# Module_Hub.net
KiCad netlist of a schematic drawn in Altium Designer
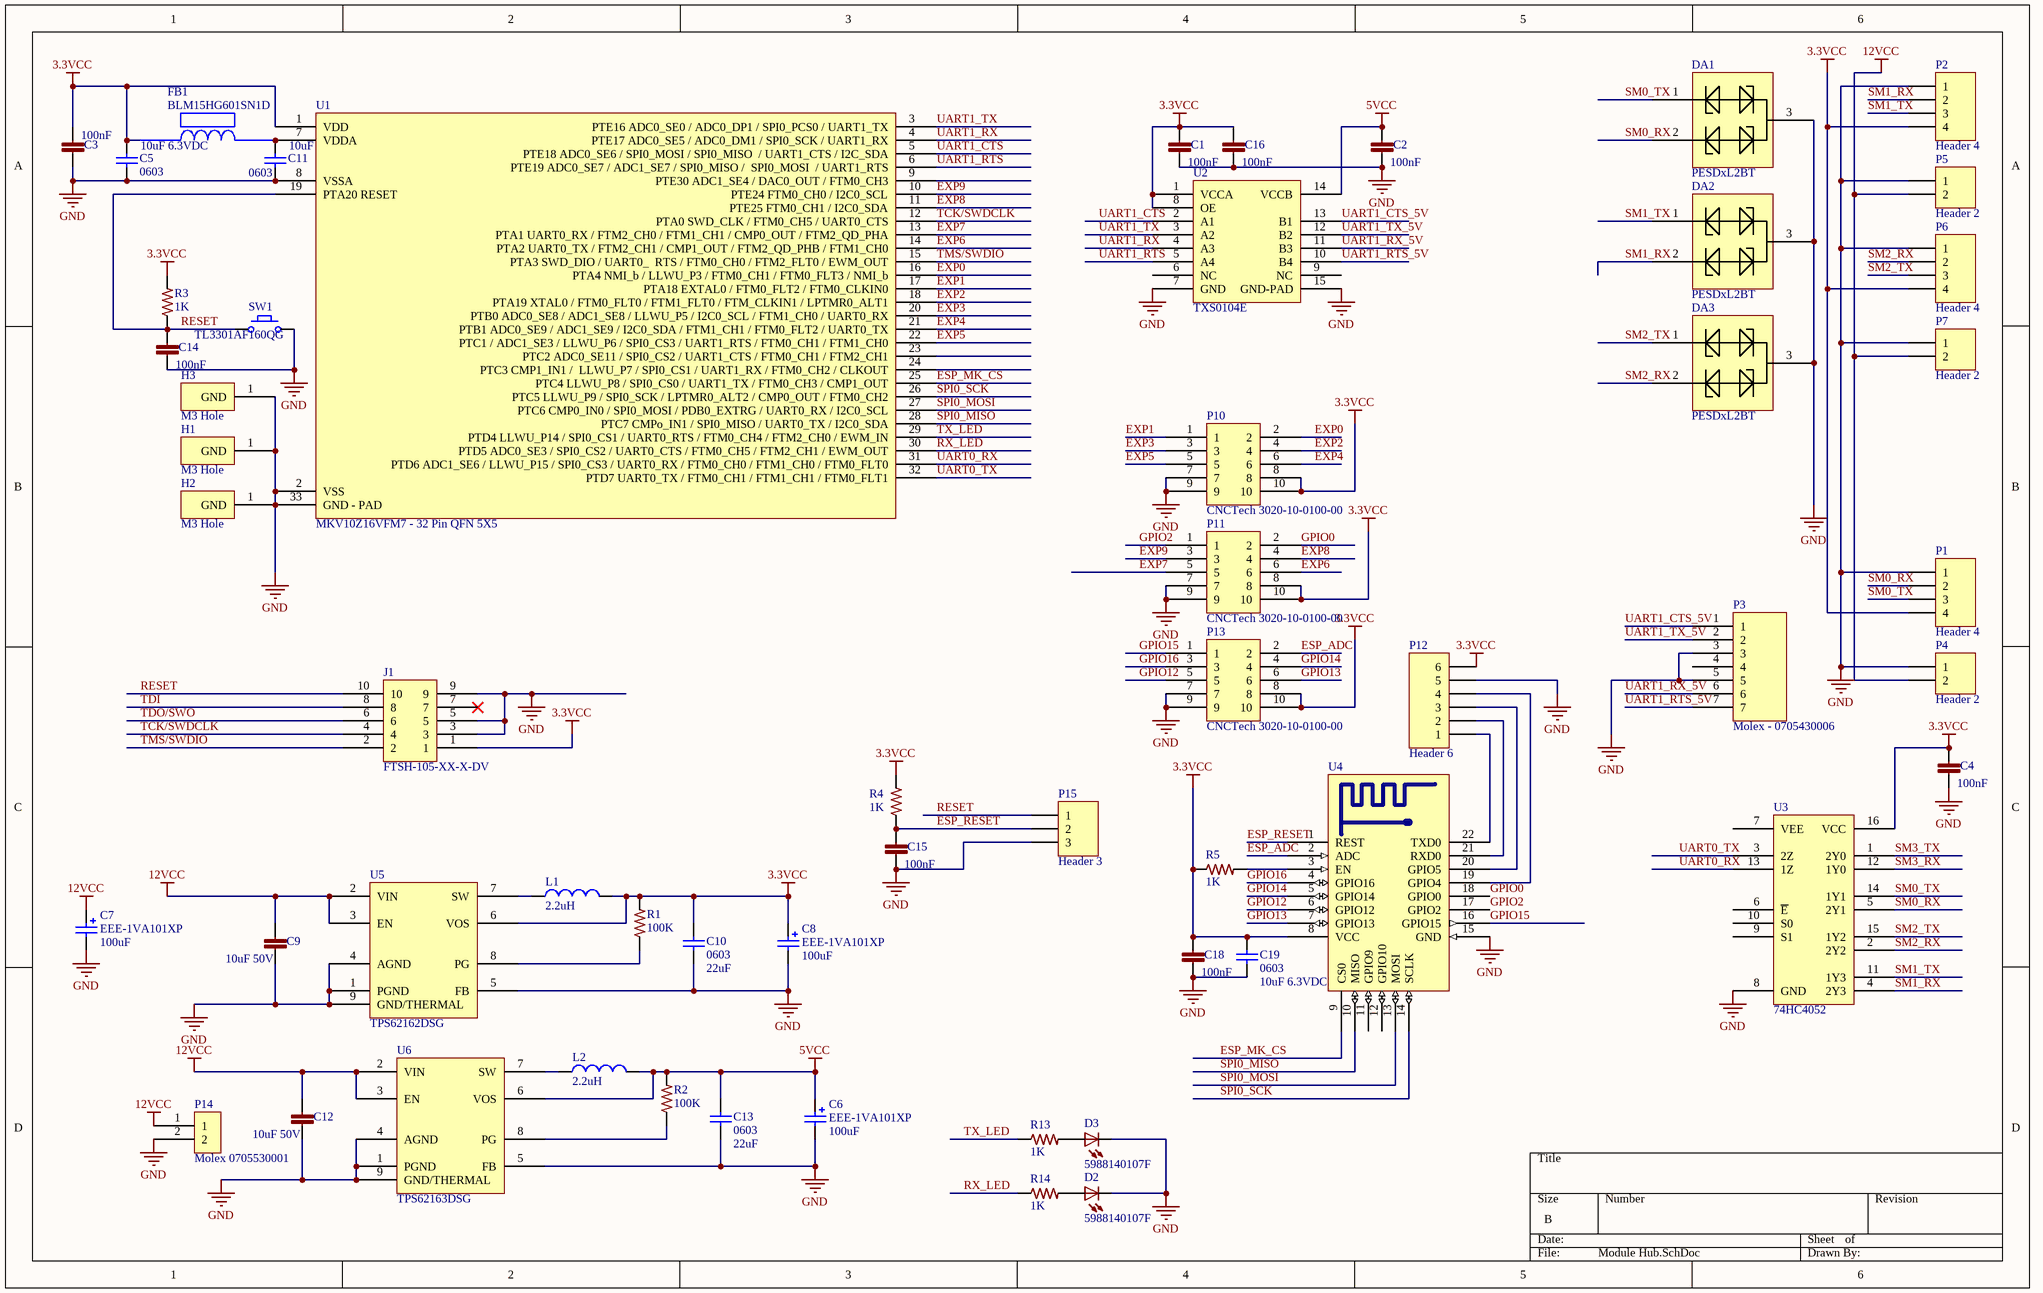
[diagram p0: Module Hub.SchDoc]

(export (version "E")
  (design (tool "Eeschema 10.0.6"))
  (components
    (comp (ref "C1")
      (value "100nF")
      (footprint "C0603")
      (description "CAP CER 0603 100nF 50V 10% X7R")
      (fields
        (field (name "MANUFACTURERPARTNUMBER") "C0603C104K5RACTU")
        (field (name "PUBLISHER") "UltiMachine")
      )
      (libsource (lib "3Delight") (part "C0603C104K5RACTU"))
    )
    (comp (ref "C2")
      (value "100nF")
      (footprint "C0603")
      (description "CAP CER 0603 100nF 50V 10% X7R")
      (fields
        (field (name "MANUFACTURERPARTNUMBER") "C0603C104K5RACTU")
        (field (name "PUBLISHER") "UltiMachine")
      )
      (libsource (lib "3Delight") (part "C0603C104K5RACTU"))
    )
    (comp (ref "C3")
      (value "100nF")
      (footprint "C0603")
      (description "CAP CER 0603 100nF 50V 10% X7R")
      (fields
        (field (name "MANUFACTURERPARTNUMBER") "C0603C104K5RACTU")
        (field (name "PUBLISHER") "UltiMachine")
      )
      (libsource (lib "3Delight") (part "C0603C104K5RACTU"))
    )
    (comp (ref "C4")
      (value "100nF")
      (footprint "C0603")
      (description "CAP CER 0603 100nF 50V 10% X7R")
      (fields
        (field (name "MANUFACTURERPARTNUMBER") "C0603C104K5RACTU")
        (field (name "PUBLISHER") "UltiMachine")
      )
      (libsource (lib "3Delight") (part "C0603C104K5RACTU"))
    )
    (comp (ref "C5")
      (value "0603")
      (footprint "C0603")
      (description "CAP CER 10UF 6.3V 10% JB 0603")
      (fields
        (field (name "MFR PART #") "C1608JB0J106K080AB")
        (field (name "MFR") "TDK")
        (field (name "ALTIUM_VALUE") "10uF 6.3VDC")
      )
      (libsource (lib "Tigershark3D") (part "C1608JB0J106K080AB"))
    )
    (comp (ref "C6")
      (value "EEE-1VA101XP")
      (footprint "EEE-1VA101XP")
      (description "CAP ALUM 100UF 35V 20% SMD")
      (fields (field (name "DIGIKEY PART #") "PCE3951CT-ND") (field (name "ALTIUM_VALUE") "100uF"))
      (libsource (lib "Tigershark3D") (part "EEE-1VA101XP"))
    )
    (comp (ref "C7")
      (value "EEE-1VA101XP")
      (footprint "EEE-1VA101XP")
      (description "CAP ALUM 100UF 35V 20% SMD")
      (fields (field (name "DIGIKEY PART #") "PCE3951CT-ND") (field (name "ALTIUM_VALUE") "100uF"))
      (libsource (lib "Tigershark3D") (part "EEE-1VA101XP"))
    )
    (comp (ref "C8")
      (value "EEE-1VA101XP")
      (footprint "EEE-1VA101XP")
      (description "CAP ALUM 100UF 35V 20% SMD")
      (fields (field (name "DIGIKEY PART #") "PCE3951CT-ND") (field (name "ALTIUM_VALUE") "100uF"))
      (libsource (lib "Tigershark3D") (part "EEE-1VA101XP"))
    )
    (comp (ref "C9")
      (value "10uF 50V")
      (footprint "C1206")
      (description "CAP CER 10UF 50V 10% X5R 1206")
      (fields
        (field (name "MANUFACTURER") "Samsung")
        (field (name "MANUFACTURERPARTNUMBER") "CL31A106KBHNNNE")
        (field (name "PUBLISHER") "UltiMachine")
      )
      (libsource (lib "Tigershark3D") (part "CL31A106KBHNNNE"))
    )
    (comp (ref "C10")
      (value "0603")
      (footprint "C0805")
      (description "CAP CER 22UF 6.3V 10% X5R 0805")
      (fields
        (field (name "MFR PART #") "CL21A226KQQNNNE")
        (field (name "MFR") "Samsung")
        (field (name "ALTIUM_VALUE") "22uF")
      )
      (libsource (lib "Sensor Package") (part "CL21A226KQQNNNE"))
    )
    (comp (ref "C11")
      (value "0603")
      (footprint "C0603")
      (description "CAP CER 10UF 6.3V 10% JB 0603")
      (fields
        (field (name "MFR PART #") "C1608JB0J106K080AB")
        (field (name "MFR") "TDK")
        (field (name "ALTIUM_VALUE") "10uF")
      )
      (libsource (lib "Tigershark3D") (part "C1608JB0J106K080AB"))
    )
    (comp (ref "C12")
      (value "10uF 50V")
      (footprint "C1206")
      (description "CAP CER 10UF 50V 10% X5R 1206")
      (fields
        (field (name "MANUFACTURER") "Samsung")
        (field (name "MANUFACTURERPARTNUMBER") "CL31A106KBHNNNE")
        (field (name "PUBLISHER") "UltiMachine")
      )
      (libsource (lib "Tigershark3D") (part "CL31A106KBHNNNE"))
    )
    (comp (ref "C13")
      (value "0603")
      (footprint "C0805")
      (description "CAP CER 22UF 6.3V 10% X5R 0805")
      (fields
        (field (name "MFR PART #") "CL21A226KQQNNNE")
        (field (name "MFR") "Samsung")
        (field (name "ALTIUM_VALUE") "22uF")
      )
      (libsource (lib "Sensor Package") (part "CL21A226KQQNNNE"))
    )
    (comp (ref "C14")
      (value "100nF")
      (footprint "C0402")
      (description "CAP CER 0402 100nF 16V 10% X7R")
      (fields
        (field (name "MANUFACTURERPARTNUMBER") "GRM155R71C104KA88D")
        (field (name "PUBLISHER") "UltiMachine")
      )
      (libsource (lib "3Delight") (part "GRM155R71C104KA88D"))
    )
    (comp (ref "C15")
      (value "100nF")
      (footprint "C0402")
      (description "CAP CER 0402 100nF 16V 10% X7R")
      (fields
        (field (name "MANUFACTURERPARTNUMBER") "GRM155R71C104KA88D")
        (field (name "PUBLISHER") "UltiMachine")
      )
      (libsource (lib "3Delight") (part "GRM155R71C104KA88D"))
    )
    (comp (ref "C16")
      (value "100nF")
      (footprint "C0603")
      (description "CAP CER 0603 100nF 50V 10% X7R")
      (fields
        (field (name "MANUFACTURERPARTNUMBER") "C0603C104K5RACTU")
        (field (name "PUBLISHER") "UltiMachine")
      )
      (libsource (lib "3Delight") (part "C0603C104K5RACTU"))
    )
    (comp (ref "C18")
      (value "100nF")
      (footprint "C0603")
      (description "CAP CER 0603 100nF 50V 10% X7R")
      (fields
        (field (name "MANUFACTURERPARTNUMBER") "C0603C104K5RACTU")
        (field (name "PUBLISHER") "UltiMachine")
      )
      (libsource (lib "3Delight") (part "C0603C104K5RACTU"))
    )
    (comp (ref "C19")
      (value "0603")
      (footprint "C0603")
      (description "CAP CER 10UF 6.3V 10% JB 0603")
      (fields
        (field (name "MFR PART #") "C1608JB0J106K080AB")
        (field (name "MFR") "TDK")
        (field (name "ALTIUM_VALUE") "10uF 6.3VDC")
      )
      (libsource (lib "Tigershark3D") (part "C1608JB0J106K080AB"))
    )
    (comp (ref "D2")
      (value "5988140107F")
      (footprint "LED2012120")
      (description "LED 0805 Yellow")
      (fields (field (name "PUBLISHER") "UltiMachine"))
      (libsource (lib "Tigershark3D") (part "5988140107F"))
    )
    (comp (ref "D3")
      (value "5988140107F")
      (footprint "LED2012120")
      (description "LED 0805 Yellow")
      (fields (field (name "PUBLISHER") "UltiMachine"))
      (libsource (lib "Tigershark3D") (part "5988140107F"))
    )
    (comp (ref "DA1")
      (value "PESDxL2BT")
      (footprint "SOT95P230X110-3N")
      (description "PESDxL2BT TVS Diode Array 2x")
      (libsource (lib "ZMBo Schematic Library") (part "PESDxL2BT"))
    )
    (comp (ref "DA2")
      (value "PESDxL2BT")
      (footprint "SOT95P230X110-3N")
      (description "PESDxL2BT TVS Diode Array 2x")
      (libsource (lib "ZMBo Schematic Library") (part "PESDxL2BT"))
    )
    (comp (ref "DA3")
      (value "PESDxL2BT")
      (footprint "SOT95P230X110-3N")
      (description "PESDxL2BT TVS Diode Array 2x")
      (libsource (lib "ZMBo Schematic Library") (part "PESDxL2BT"))
    )
    (comp (ref "FB1")
      (value "BLM15HG601SN1D")
      (footprint "BLM18PG121SN1D")
      (libsource (lib "AHD Part Library") (part "BLM15HG601SN1D"))
    )
    (comp (ref "H1")
      (value "M3 Hole")
      (footprint "Hole-3mm")
      (description "3mm Hole")
      (libsource (lib "Sensor Package") (part "Hole"))
    )
    (comp (ref "H2")
      (value "M3 Hole")
      (footprint "Hole-3mm")
      (description "3mm Hole")
      (libsource (lib "Sensor Package") (part "Hole"))
    )
    (comp (ref "H3")
      (value "M3 Hole")
      (footprint "Hole-3mm")
      (description "3mm Hole")
      (libsource (lib "Sensor Package") (part "Hole"))
    )
    (comp (ref "J1")
      (value "FTSH-105-XX-X-DV")
      (footprint "FTSH-105-XX-X-DV")
      (libsource (lib "Adams Altium Library") (part "ARM Cortex JTAG-DEBUG Header"))
    )
    (comp (ref "L1")
      (value "2.2uH")
      (footprint "VLS252012T-2R2M1R3")
      (description "VLS252012T-2R2M1R3")
      (fields (field (name "MFR") "TDK Corporation") (field (name "PUBLISHER") "Adam Vadala-Roth"))
      (libsource (lib "Sensor Package") (part "VLS252012T-2R2M1R3"))
    )
    (comp (ref "L2")
      (value "2.2uH")
      (footprint "VLS252012T-2R2M1R3")
      (description "VLS252012T-2R2M1R3")
      (fields (field (name "MFR") "TDK Corporation") (field (name "PUBLISHER") "Adam Vadala-Roth"))
      (libsource (lib "Sensor Package") (part "VLS252012T-2R2M1R3"))
    )
    (comp (ref "P1")
      (value "Header 4")
      (footprint "HDR1X4")
      (description "Header, 4-Pin")
      (fields (field (name "PUBLISHER") "Altium Limited"))
      (libsource (lib "Miscellaneous Connectors") (part "Header 4"))
    )
    (comp (ref "P2")
      (value "Header 4")
      (footprint "HDR1X4")
      (description "Header, 4-Pin")
      (fields (field (name "PUBLISHER") "Altium Limited"))
      (libsource (lib "Miscellaneous Connectors") (part "Header 4"))
    )
    (comp (ref "P3")
      (value "Molex - 0705430006")
      (footprint "0705530041")
      (description "0705530041")
      (fields (field (name "MFR") "Molex"))
      (libsource (lib "Sensor Package") (part "0705530041"))
    )
    (comp (ref "P4")
      (value "Header 2")
      (footprint "HDR1X2")
      (description "Header, 2-Pin")
      (fields (field (name "PUBLISHER") "Altium Limited"))
      (libsource (lib "Miscellaneous Connectors") (part "Header 2"))
    )
    (comp (ref "P5")
      (value "Header 2")
      (footprint "HDR1X2")
      (description "Header, 2-Pin")
      (fields (field (name "PUBLISHER") "Altium Limited"))
      (libsource (lib "Miscellaneous Connectors") (part "Header 2"))
    )
    (comp (ref "P6")
      (value "Header 4")
      (footprint "HDR1X4")
      (description "Header, 4-Pin")
      (fields (field (name "PUBLISHER") "Altium Limited"))
      (libsource (lib "Miscellaneous Connectors") (part "Header 4"))
    )
    (comp (ref "P7")
      (value "Header 2")
      (footprint "HDR1X2")
      (description "Header, 2-Pin")
      (fields (field (name "PUBLISHER") "Altium Limited"))
      (libsource (lib "Miscellaneous Connectors") (part "Header 2"))
    )
    (comp (ref "P10")
      (value "CNCTech 3020-10-0100-00")
      (footprint "3020-10-0100-00")
      (fields
        (field (name "MANUFACTURE PART #") "3020-10-0100-00")
        (field (name "MANUFACTURER") "CNCTech")
        (field (name "DIGIKEY PART #") "1175-1609-ND")
      )
      (libsource (lib "Tigershark3D") (part "3020-10-0100-00"))
    )
    (comp (ref "P11")
      (value "CNCTech 3020-10-0100-00")
      (footprint "3020-10-0100-00")
      (fields
        (field (name "MANUFACTURE PART #") "3020-10-0100-00")
        (field (name "MANUFACTURER") "CNCTech")
        (field (name "DIGIKEY PART #") "1175-1609-ND")
      )
      (libsource (lib "Tigershark3D") (part "3020-10-0100-00"))
    )
    (comp (ref "P12")
      (value "Header 6")
      (footprint "HDR1X6")
      (description "Header, 6-Pin")
      (fields (field (name "PUBLISHER") "Altium Limited"))
      (libsource (lib "Miscellaneous Connectors") (part "Header 6"))
    )
    (comp (ref "P13")
      (value "CNCTech 3020-10-0100-00")
      (footprint "3020-10-0100-00")
      (fields
        (field (name "MANUFACTURE PART #") "3020-10-0100-00")
        (field (name "MANUFACTURER") "CNCTech")
        (field (name "DIGIKEY PART #") "1175-1609-ND")
      )
      (libsource (lib "Tigershark3D") (part "3020-10-0100-00"))
    )
    (comp (ref "P14")
      (value "Molex 0705530001")
      (footprint "0705530001")
      (description "Molex 0705530002 Right Angle 2.54mm Shrouded Header")
      (fields (field (name "MFR") "Molex"))
      (libsource (lib "Sensor Package") (part "0705530001"))
    )
    (comp (ref "P15")
      (value "Header 3")
      (footprint "HDR1X3")
      (description "Header, 3-Pin")
      (fields (field (name "PUBLISHER") "Altium Limited"))
      (libsource (lib "Miscellaneous Connectors") (part "Header 3"))
    )
    (comp (ref "R1")
      (value "100K")
      (footprint "R0603")
      (description "RES 100K OHM 1/10W 1% 0603 SMD")
      (fields
        (field (name "MANUFACTURERPARTNUMBER") "RC0603FR-07100KL")
        (field (name "PUBLISHER") "UltiMachine")
      )
      (libsource (lib "3Delight") (part "RC0603FR-07100KL"))
    )
    (comp (ref "R2")
      (value "100K")
      (footprint "R0603")
      (description "RES 100K OHM 1/10W 1% 0603 SMD")
      (fields
        (field (name "MANUFACTURERPARTNUMBER") "RC0603FR-07100KL")
        (field (name "PUBLISHER") "UltiMachine")
      )
      (libsource (lib "3Delight") (part "RC0603FR-07100KL"))
    )
    (comp (ref "R3")
      (value "1K")
      (footprint "R0603")
      (description "RES 0603 1K 100mW 1%")
      (fields
        (field (name "MANUFACTURERPARTNUMBER") "ERJ-3EKF1001V")
        (field (name "PUBLISHER") "UltiMachine")
      )
      (libsource (lib "3Delight") (part "ERJ-3EKF1001V"))
    )
    (comp (ref "R4")
      (value "1K")
      (footprint "R0603")
      (description "RES 0603 1K 100mW 1%")
      (fields
        (field (name "MANUFACTURERPARTNUMBER") "ERJ-3EKF1001V")
        (field (name "PUBLISHER") "UltiMachine")
      )
      (libsource (lib "3Delight") (part "ERJ-3EKF1001V"))
    )
    (comp (ref "R5")
      (value "1K")
      (footprint "R0603")
      (description "RES 0603 1K 100mW 1%")
      (fields
        (field (name "MANUFACTURERPARTNUMBER") "ERJ-3EKF1001V")
        (field (name "PUBLISHER") "UltiMachine")
      )
      (libsource (lib "Tigershark3D") (part "ERJ-3EKF1001V"))
    )
    (comp (ref "R13")
      (value "1K")
      (footprint "R0603")
      (description "RES 0603 1K 100mW 1%")
      (fields
        (field (name "MANUFACTURERPARTNUMBER") "ERJ-3EKF1001V")
        (field (name "PUBLISHER") "UltiMachine")
      )
      (libsource (lib "Tigershark3D") (part "ERJ-3EKF1001V"))
    )
    (comp (ref "R14")
      (value "1K")
      (footprint "R0603")
      (description "RES 0603 1K 100mW 1%")
      (fields
        (field (name "MANUFACTURERPARTNUMBER") "ERJ-3EKF1001V")
        (field (name "PUBLISHER") "UltiMachine")
      )
      (libsource (lib "Tigershark3D") (part "ERJ-3EKF1001V"))
    )
    (comp (ref "SW1")
      (value "TL3301AF160QG")
      (footprint "TL3301AF160QG")
      (libsource (lib "MongoosMini") (part "TL3301AF160QG"))
    )
    (comp (ref "U1")
      (value "MKV10Z16VFM7 - 32 Pin QFN 5X5")
      (footprint "MKV10Z16VFM7")
      (description "IC MCU ARM Cortex M0+ 16KB 32QFN 75MHZ")
      (fields (field (name "MFR") "FreeScale"))
      (libsource (lib "Sensor Package") (part "MKV10Z16VFM7"))
    )
    (comp (ref "U2")
      (value "TXS0104E")
      (footprint "RGY  (S-PVQFN-N14)")
      (description "TXS0104E - Bidriectional Opendrain/pushpull level shift")
      (fields (field (name "MFR") "Texas Instruments") (field (name "MFR PART #") "TXS0104ERGYR"))
      (libsource (lib "Tigershark3D") (part "TXS0104E"))
    )
    (comp (ref "U3")
      (value "74HC4052")
      (footprint "74HC4052")
      (description "Dual 4-channel analog multiplexer/demultiplexer")
      (fields (field (name "MFR") "NXP"))
      (libsource (lib "Sensor Package") (part "74HC4052"))
    )
    (comp (ref "U4")
      (value "ESP-12E")
      (footprint "ESP8266 ESP-12E")
      (description "Sketchy Chinese ESP8266 Board with Fake FCC Bullshit")
      (libsource (lib "Sensor Package") (part "ESP-12"))
    )
    (comp (ref "U5")
      (value "TPS62162DSG")
      (footprint "DSG8-1600X900TP")
      (libsource (lib "Adams Altium Library") (part "TPS62162SOP"))
    )
    (comp (ref "U6")
      (value "TPS62163DSG")
      (footprint "DSG8-1600X900TP")
      (libsource (lib "Adams Altium Library") (part "TPS62162SOP"))
    )
  )
  (nets
    (net (code "1") (name "/ESP_ADC") (class "Default")
      (node (ref "P13") (pin "2") (pinfunction "2_2") (pintype "passive"))
      (node (ref "U4") (pin "2") (pinfunction "ADC_2") (pintype "input"))
    )
    (net (code "2") (name "/ESP_MK_CS") (class "Default")
      (node (ref "U1") (pin "25") (pinfunction "PTC4_LLWU_P8_/_SPI0_CS0_/_UART1_TX_/_FTM0_CH3_/_CMP1_OUT_25") (pintype "passive"))
      (node (ref "U4") (pin "9") (pinfunction "CS0_9") (pintype "power_in"))
    )
    (net (code "3") (name "/ESP_RESET") (class "Default")
      (node (ref "C15") (pin "1") (pinfunction "1_1") (pintype "passive"))
      (node (ref "P15") (pin "2") (pinfunction "2_2") (pintype "passive"))
      (node (ref "R4") (pin "1") (pinfunction "1_1") (pintype "passive"))
      (node (ref "U4") (pin "1") (pinfunction "REST_1") (pintype "passive"))
    )
    (net (code "4") (name "/EXP0") (class "Default")
      (node (ref "P10") (pin "2") (pinfunction "2_2") (pintype "passive"))
      (node (ref "U1") (pin "16") (pinfunction "PTA4_NMI_b_/_LLWU_P3_/_FTM0_CH1_/_FTM0_FLT3_/_NMI_b_16") (pintype "passive"))
    )
    (net (code "5") (name "/EXP1") (class "Default")
      (node (ref "P10") (pin "1") (pinfunction "1_1") (pintype "passive"))
      (node (ref "U1") (pin "17") (pinfunction "PTA18_EXTAL0_/_FTM0_FLT2_/_FTM0_CLKIN0_17") (pintype "passive"))
    )
    (net (code "6") (name "/EXP2") (class "Default")
      (node (ref "P10") (pin "4") (pinfunction "4_4") (pintype "passive"))
      (node (ref "U1") (pin "18") (pinfunction "PTA19_XTAL0_/_FTM0_FLT0_/_FTM1_FLT0_/_FTM_CLKIN1_/_LPTMR0_ALT1_18") (pintype "passive"))
    )
    (net (code "7") (name "/EXP3") (class "Default")
      (node (ref "P10") (pin "3") (pinfunction "3_3") (pintype "passive"))
      (node (ref "U1") (pin "20") (pinfunction "PTB0_ADC0_SE8_/_ADC1_SE8_/_LLWU_P5_/_I2C0_SCL_/_FTM1_CH0_/_UART0_RX_20") (pintype "passive"))
    )
    (net (code "8") (name "/EXP4") (class "Default")
      (node (ref "P10") (pin "6") (pinfunction "6_6") (pintype "passive"))
      (node (ref "U1") (pin "21") (pinfunction "PTB1_ADC0_SE9_/_ADC1_SE9_/_I2C0_SDA_/_FTM1_CH1_/_FTM0_FLT2_/_UART0_TX_21") (pintype "passive"))
    )
    (net (code "9") (name "/EXP5") (class "Default")
      (node (ref "P10") (pin "5") (pinfunction "5_5") (pintype "passive"))
      (node (ref "U1") (pin "22") (pinfunction "PTC1_/_ADC1_SE3_/_LLWU_P6_/_SPI0_CS3_/_UART1_RTS_/_FTM0_CH1_/_FTM1_CH0_22") (pintype "passive"))
    )
    (net (code "10") (name "/EXP6") (class "Default")
      (node (ref "P11") (pin "6") (pinfunction "6_6") (pintype "passive"))
      (node (ref "U1") (pin "14") (pinfunction "PTA2_UART0_TX_/_FTM2_CH1_/_CMP1_OUT_/_FTM2_QD_PHB_/_FTM1_CH0_14") (pintype "passive"))
    )
    (net (code "11") (name "/EXP7") (class "Default")
      (node (ref "P11") (pin "5") (pinfunction "5_5") (pintype "passive"))
      (node (ref "U1") (pin "13") (pinfunction "PTA1_UART0_RX_/_FTM2_CH0_/_FTM1_CH1_/_CMP0_OUT_/_FTM2_QD_PHA_13") (pintype "passive"))
    )
    (net (code "12") (name "/EXP8") (class "Default")
      (node (ref "P11") (pin "4") (pinfunction "4_4") (pintype "passive"))
      (node (ref "U1") (pin "11") (pinfunction "PTE25_FTM0_CH1_/_I2C0_SDA_11") (pintype "passive"))
    )
    (net (code "13") (name "/EXP9") (class "Default")
      (node (ref "P11") (pin "3") (pinfunction "3_3") (pintype "passive"))
      (node (ref "U1") (pin "10") (pinfunction "PTE24_FTM0_CH0_/_I2C0_SCL_10") (pintype "passive"))
    )
    (net (code "14") (name "/GPIO0") (class "Default")
      (node (ref "P11") (pin "2") (pinfunction "2_2") (pintype "passive"))
      (node (ref "U4") (pin "18") (pinfunction "GPIO0_18") (pintype "passive"))
    )
    (net (code "15") (name "/GPIO2") (class "Default")
      (node (ref "P11") (pin "1") (pinfunction "1_1") (pintype "passive"))
      (node (ref "U4") (pin "17") (pinfunction "GPIO2_17") (pintype "passive"))
    )
    (net (code "16") (name "/GPIO12") (class "Default")
      (node (ref "P13") (pin "5") (pinfunction "5_5") (pintype "passive"))
      (node (ref "U4") (pin "6") (pinfunction "GPIO12_6") (pintype "bidirectional"))
    )
    (net (code "17") (name "/GPIO13") (class "Default")
      (node (ref "P13") (pin "6") (pinfunction "6_6") (pintype "passive"))
      (node (ref "U4") (pin "7") (pinfunction "GPIO13_7") (pintype "bidirectional"))
    )
    (net (code "18") (name "/GPIO14") (class "Default")
      (node (ref "P13") (pin "4") (pinfunction "4_4") (pintype "passive"))
      (node (ref "U4") (pin "5") (pinfunction "GPIO14_5") (pintype "bidirectional"))
    )
    (net (code "19") (name "/GPIO15") (class "Default")
      (node (ref "P13") (pin "1") (pinfunction "1_1") (pintype "passive"))
      (node (ref "U4") (pin "16") (pinfunction "GPIO15_16") (pintype "output"))
    )
    (net (code "20") (name "/GPIO16") (class "Default")
      (node (ref "P13") (pin "3") (pinfunction "3_3") (pintype "passive"))
      (node (ref "U4") (pin "4") (pinfunction "GPIO16_4") (pintype "bidirectional"))
    )
    (net (code "21") (name "/RESET") (class "Default")
      (node (ref "C14") (pin "1") (pinfunction "1_1") (pintype "passive"))
      (node (ref "J1") (pin "10") (pinfunction "10_10") (pintype "passive"))
      (node (ref "P15") (pin "1") (pinfunction "1_1") (pintype "passive"))
      (node (ref "R3") (pin "1") (pinfunction "1_1") (pintype "passive"))
      (node (ref "SW1") (pin "1") (pintype "passive"))
      (node (ref "U1") (pin "19") (pinfunction "PTA20_RESET_19") (pintype "passive"))
    )
    (net (code "22") (name "/RX_LED") (class "Default")
      (node (ref "R14") (pin "1") (pinfunction "1_1") (pintype "passive"))
      (node (ref "U1") (pin "30") (pinfunction "PTD5_ADC0_SE3_/_SPI0_CS2_/_UART0_CTS_/_FTM0_CH5_/_FTM2_CH1_/_EWM_OUT_30") (pintype "passive"))
    )
    (net (code "23") (name "/SM0_RX") (class "Default")
      (node (ref "DA1") (pin "2") (pinfunction "2_2") (pintype "passive"))
      (node (ref "P1") (pin "2") (pinfunction "2_2") (pintype "passive"))
      (node (ref "U3") (pin "5") (pinfunction "2Y1_5") (pintype "passive"))
    )
    (net (code "24") (name "/SM0_TX") (class "Default")
      (node (ref "DA1") (pin "1") (pinfunction "1_1") (pintype "passive"))
      (node (ref "P1") (pin "3") (pinfunction "3_3") (pintype "passive"))
      (node (ref "U3") (pin "14") (pinfunction "1Y1_14") (pintype "passive"))
    )
    (net (code "25") (name "/SM1_RX") (class "Default")
      (node (ref "DA2") (pin "2") (pinfunction "2_2") (pintype "passive"))
      (node (ref "P2") (pin "2") (pinfunction "2_2") (pintype "passive"))
      (node (ref "U3") (pin "4") (pinfunction "2Y3_4") (pintype "passive"))
    )
    (net (code "26") (name "/SM1_TX") (class "Default")
      (node (ref "DA2") (pin "1") (pinfunction "1_1") (pintype "passive"))
      (node (ref "P2") (pin "3") (pinfunction "3_3") (pintype "passive"))
      (node (ref "U3") (pin "11") (pinfunction "1Y3_11") (pintype "passive"))
    )
    (net (code "27") (name "/SM2_RX") (class "Default")
      (node (ref "DA3") (pin "2") (pinfunction "2_2") (pintype "passive"))
      (node (ref "P6") (pin "2") (pinfunction "2_2") (pintype "passive"))
      (node (ref "U3") (pin "2") (pinfunction "2Y2_2") (pintype "passive"))
    )
    (net (code "28") (name "/SM2_TX") (class "Default")
      (node (ref "DA3") (pin "1") (pinfunction "1_1") (pintype "passive"))
      (node (ref "P6") (pin "3") (pinfunction "3_3") (pintype "passive"))
      (node (ref "U3") (pin "15") (pinfunction "1Y2_15") (pintype "passive"))
    )
    (net (code "29") (name "/SM3_RX") (class "Default")
      (node (ref "U3") (pin "12") (pinfunction "1Y0_12") (pintype "passive"))
    )
    (net (code "30") (name "/SM3_TX") (class "Default")
      (node (ref "U3") (pin "1") (pinfunction "2Y0_1") (pintype "passive"))
    )
    (net (code "31") (name "/SPI0_MISO") (class "Default")
      (node (ref "U1") (pin "28") (pinfunction "PTC7_CMPo_IN1_/_SPI0_MISO_/_UART0_TX_/_I2C0_SDA_28") (pintype "passive"))
      (node (ref "U4") (pin "10") (pinfunction "MISO_10") (pintype "bidirectional"))
    )
    (net (code "32") (name "/SPI0_MOSI") (class "Default")
      (node (ref "U1") (pin "27") (pinfunction "PTC6_CMP0_IN0_/_SPI0_MOSI_/_PDB0_EXTRG_/_UART0_RX_/_I2C0_SCL_27") (pintype "passive"))
      (node (ref "U4") (pin "13") (pinfunction "MOSI_13") (pintype "bidirectional"))
    )
    (net (code "33") (name "/SPI0_SCK") (class "Default")
      (node (ref "U1") (pin "26") (pinfunction "PTC5_LLWU_P9_/_SPI0_SCK_/_LPTMR0_ALT2_/_CMP0_OUT_/_FTM0_CH2_26") (pintype "passive"))
      (node (ref "U4") (pin "14") (pinfunction "SCLK_14") (pintype "bidirectional"))
    )
    (net (code "34") (name "/TCK{slash}SWDCLK") (class "Default")
      (node (ref "J1") (pin "4") (pinfunction "4_4") (pintype "passive"))
      (node (ref "U1") (pin "12") (pinfunction "PTA0_SWD_CLK_/_FTM0_CH5_/_UART0_CTS_12") (pintype "passive"))
    )
    (net (code "35") (name "/TDI") (class "Default")
      (node (ref "J1") (pin "8") (pinfunction "8_8") (pintype "passive"))
    )
    (net (code "36") (name "/TDO{slash}SWO") (class "Default")
      (node (ref "J1") (pin "6") (pinfunction "6_6") (pintype "passive"))
    )
    (net (code "37") (name "/TMS{slash}SWDIO") (class "Default")
      (node (ref "J1") (pin "2") (pinfunction "2_2") (pintype "passive"))
      (node (ref "U1") (pin "15") (pinfunction "PTA3_SWD_DIO_/_UART0___RTS_/_FTM0_CH0_/_FTM2_FLT0_/_EWM_OUT_15") (pintype "passive"))
    )
    (net (code "38") (name "/TX_LED") (class "Default")
      (node (ref "R13") (pin "1") (pinfunction "1_1") (pintype "passive"))
      (node (ref "U1") (pin "29") (pinfunction "PTD4_LLWU_P14_/_SPI0_CS1_/_UART0_RTS_/_FTM0_CH4_/_FTM2_CH0_/_EWM_IN_29") (pintype "passive"))
    )
    (net (code "39") (name "/UART0_RX") (class "Default")
      (node (ref "U1") (pin "31") (pinfunction "PTD6_ADC1_SE6_/_LLWU_P15_/_SPI0_CS3_/_UART0_RX_/_FTM0_CH0_/_FTM1_CH0_/_FTM0_FLT0_31") (pintype "passive"))
      (node (ref "U3") (pin "13") (pinfunction "1Z_13") (pintype "passive"))
    )
    (net (code "40") (name "/UART0_TX") (class "Default")
      (node (ref "U1") (pin "32") (pinfunction "PTD7_UART0_TX_/_FTM0_CH1_/_FTM1_CH1_/_FTM0_FLT1_32") (pintype "passive"))
      (node (ref "U3") (pin "3") (pinfunction "2Z_3") (pintype "passive"))
    )
    (net (code "41") (name "/UART1_CTS") (class "Default")
      (node (ref "U1") (pin "5") (pinfunction "PTE18_ADC0_SE6_/_SPI0_MOSI_/_SPI0_MISO__/_UART1_CTS_/_I2C_SDA_5") (pintype "passive"))
      (node (ref "U2") (pin "2") (pinfunction "A1_2") (pintype "passive"))
    )
    (net (code "42") (name "/UART1_CTS_5V") (class "Default")
      (node (ref "P3") (pin "1") (pinfunction "1_1") (pintype "passive"))
      (node (ref "U2") (pin "13") (pinfunction "B1_13") (pintype "passive"))
    )
    (net (code "43") (name "/UART1_RTS") (class "Default")
      (node (ref "U1") (pin "6") (pinfunction "PTE19_ADC0_SE7_/_ADC1_SE7_/_SPI0_MISO_/__SPI0_MOSI__/_UART1_RTS_6") (pintype "passive"))
      (node (ref "U2") (pin "5") (pinfunction "A4_5") (pintype "passive"))
    )
    (net (code "44") (name "/UART1_RTS_5V") (class "Default")
      (node (ref "P3") (pin "7") (pinfunction "7_7") (pintype "passive"))
      (node (ref "U2") (pin "10") (pinfunction "B4_10") (pintype "passive"))
    )
    (net (code "45") (name "/UART1_RX") (class "Default")
      (node (ref "U1") (pin "4") (pinfunction "PTE17_ADC0_SE5_/_ADC0_DM1_/_SPI0_SCK_/_UART1_RX_4") (pintype "passive"))
      (node (ref "U2") (pin "4") (pinfunction "A3_4") (pintype "passive"))
    )
    (net (code "46") (name "/UART1_RX_5V") (class "Default")
      (node (ref "P3") (pin "6") (pinfunction "6_6") (pintype "passive"))
      (node (ref "U2") (pin "11") (pinfunction "B3_11") (pintype "passive"))
    )
    (net (code "47") (name "/UART1_TX") (class "Default")
      (node (ref "U1") (pin "3") (pinfunction "PTE16_ADC0_SE0_/_ADC0_DP1_/_SPI0_PCS0_/_UART1_TX_3") (pintype "passive"))
      (node (ref "U2") (pin "3") (pinfunction "A2_3") (pintype "passive"))
    )
    (net (code "48") (name "/UART1_TX_5V") (class "Default")
      (node (ref "P3") (pin "2") (pinfunction "2_2") (pintype "passive"))
      (node (ref "U2") (pin "12") (pinfunction "B2_12") (pintype "passive"))
    )
    (net (code "49") (name "3.3VCC") (class "Default")
      (node (ref "C1") (pin "1") (pinfunction "1_1") (pintype "passive"))
      (node (ref "C10") (pin "2") (pinfunction "2_2") (pintype "passive"))
      (node (ref "C16") (pin "1") (pinfunction "1_1") (pintype "passive"))
      (node (ref "C18") (pin "1") (pinfunction "1_1") (pintype "passive"))
      (node (ref "C19") (pin "2") (pinfunction "2_2") (pintype "passive"))
      (node (ref "C3") (pin "1") (pinfunction "1_1") (pintype "passive"))
      (node (ref "C4") (pin "1") (pinfunction "1_1") (pintype "passive"))
      (node (ref "C5") (pin "2") (pinfunction "2_2") (pintype "passive"))
      (node (ref "C8") (pin "1") (pinfunction "1_1") (pintype "passive"))
      (node (ref "FB1") (pin "1") (pinfunction "1_1") (pintype "passive"))
      (node (ref "J1") (pin "1") (pinfunction "1_1") (pintype "passive"))
      (node (ref "L1") (pin "2") (pinfunction "2_2") (pintype "passive"))
      (node (ref "P1") (pin "4") (pinfunction "4_4") (pintype "passive"))
      (node (ref "P10") (pin "10") (pinfunction "10_10") (pintype "passive"))
      (node (ref "P10") (pin "8") (pinfunction "8_8") (pintype "passive"))
      (node (ref "P11") (pin "10") (pinfunction "10_10") (pintype "passive"))
      (node (ref "P11") (pin "8") (pinfunction "8_8") (pintype "passive"))
      (node (ref "P12") (pin "6") (pinfunction "6_6") (pintype "passive"))
      (node (ref "P13") (pin "10") (pinfunction "10_10") (pintype "passive"))
      (node (ref "P13") (pin "8") (pinfunction "8_8") (pintype "passive"))
      (node (ref "P2") (pin "4") (pinfunction "4_4") (pintype "passive"))
      (node (ref "P6") (pin "4") (pinfunction "4_4") (pintype "passive"))
      (node (ref "R1") (pin "2") (pinfunction "2_2") (pintype "passive"))
      (node (ref "R3") (pin "2") (pinfunction "2_2") (pintype "passive"))
      (node (ref "R4") (pin "2") (pinfunction "2_2") (pintype "passive"))
      (node (ref "R5") (pin "1") (pinfunction "1_1") (pintype "passive"))
      (node (ref "U1") (pin "1") (pinfunction "VDD_1") (pintype "passive"))
      (node (ref "U2") (pin "1") (pinfunction "VCCA_1") (pintype "passive"))
      (node (ref "U2") (pin "8") (pinfunction "OE_8") (pintype "passive"))
      (node (ref "U3") (pin "16") (pinfunction "VCC_16") (pintype "passive"))
      (node (ref "U4") (pin "8") (pinfunction "VCC_8") (pintype "power_in"))
      (node (ref "U5") (pin "6") (pinfunction "VOS_6") (pintype "passive"))
    )
    (net (code "50") (name "5VCC") (class "Default")
      (node (ref "C13") (pin "2") (pinfunction "2_2") (pintype "passive"))
      (node (ref "C2") (pin "1") (pinfunction "1_1") (pintype "passive"))
      (node (ref "C6") (pin "1") (pinfunction "1_1") (pintype "passive"))
      (node (ref "L2") (pin "2") (pinfunction "2_2") (pintype "passive"))
      (node (ref "R2") (pin "2") (pinfunction "2_2") (pintype "passive"))
      (node (ref "U2") (pin "14") (pinfunction "VCCB_14") (pintype "passive"))
      (node (ref "U6") (pin "6") (pinfunction "VOS_6") (pintype "passive"))
    )
    (net (code "51") (name "12VCC") (class "Default")
      (node (ref "C12") (pin "1") (pinfunction "1_1") (pintype "passive"))
      (node (ref "C7") (pin "1") (pinfunction "1_1") (pintype "passive"))
      (node (ref "C9") (pin "1") (pinfunction "1_1") (pintype "passive"))
      (node (ref "P14") (pin "1") (pinfunction "1_1") (pintype "passive"))
      (node (ref "P4") (pin "2") (pinfunction "2_2") (pintype "passive"))
      (node (ref "P5") (pin "2") (pinfunction "2_2") (pintype "passive"))
      (node (ref "P7") (pin "2") (pinfunction "2_2") (pintype "passive"))
      (node (ref "U5") (pin "2") (pinfunction "VIN_2") (pintype "passive"))
      (node (ref "U5") (pin "3") (pinfunction "EN_3") (pintype "passive"))
      (node (ref "U6") (pin "2") (pinfunction "VIN_2") (pintype "passive"))
      (node (ref "U6") (pin "3") (pinfunction "EN_3") (pintype "passive"))
    )
    (net (code "52") (name "GND") (class "Default")
      (node (ref "C1") (pin "2") (pinfunction "2_2") (pintype "passive"))
      (node (ref "C10") (pin "1") (pinfunction "1_1") (pintype "passive"))
      (node (ref "C11") (pin "1") (pinfunction "1_1") (pintype "passive"))
      (node (ref "C12") (pin "2") (pinfunction "2_2") (pintype "passive"))
      (node (ref "C13") (pin "1") (pinfunction "1_1") (pintype "passive"))
      (node (ref "C14") (pin "2") (pinfunction "2_2") (pintype "passive"))
      (node (ref "C15") (pin "2") (pinfunction "2_2") (pintype "passive"))
      (node (ref "C16") (pin "2") (pinfunction "2_2") (pintype "passive"))
      (node (ref "C18") (pin "2") (pinfunction "2_2") (pintype "passive"))
      (node (ref "C19") (pin "1") (pinfunction "1_1") (pintype "passive"))
      (node (ref "C2") (pin "2") (pinfunction "2_2") (pintype "passive"))
      (node (ref "C3") (pin "2") (pinfunction "2_2") (pintype "passive"))
      (node (ref "C4") (pin "2") (pinfunction "2_2") (pintype "passive"))
      (node (ref "C5") (pin "1") (pinfunction "1_1") (pintype "passive"))
      (node (ref "C6") (pin "2") (pinfunction "2_2") (pintype "passive"))
      (node (ref "C7") (pin "2") (pinfunction "2_2") (pintype "passive"))
      (node (ref "C8") (pin "2") (pinfunction "2_2") (pintype "passive"))
      (node (ref "C9") (pin "2") (pinfunction "2_2") (pintype "passive"))
      (node (ref "D2") (pin "C") (pinfunction "C_C") (pintype "passive"))
      (node (ref "D3") (pin "C") (pinfunction "C_C") (pintype "passive"))
      (node (ref "DA1") (pin "3") (pinfunction "3_3") (pintype "passive"))
      (node (ref "DA2") (pin "3") (pinfunction "3_3") (pintype "passive"))
      (node (ref "DA3") (pin "3") (pinfunction "3_3") (pintype "passive"))
      (node (ref "H1") (pin "1") (pinfunction "GND_1") (pintype "passive"))
      (node (ref "H2") (pin "1") (pinfunction "GND_1") (pintype "passive"))
      (node (ref "H3") (pin "1") (pinfunction "GND_1") (pintype "passive"))
      (node (ref "J1") (pin "3") (pinfunction "3_3") (pintype "passive"))
      (node (ref "J1") (pin "5") (pinfunction "5_5") (pintype "passive"))
      (node (ref "J1") (pin "9") (pinfunction "9_9") (pintype "passive"))
      (node (ref "P1") (pin "1") (pinfunction "1_1") (pintype "passive"))
      (node (ref "P10") (pin "7") (pinfunction "7_7") (pintype "passive"))
      (node (ref "P10") (pin "9") (pinfunction "9_9") (pintype "passive"))
      (node (ref "P11") (pin "7") (pinfunction "7_7") (pintype "passive"))
      (node (ref "P11") (pin "9") (pinfunction "9_9") (pintype "passive"))
      (node (ref "P12") (pin "5") (pinfunction "5_5") (pintype "passive"))
      (node (ref "P13") (pin "7") (pinfunction "7_7") (pintype "passive"))
      (node (ref "P13") (pin "9") (pinfunction "9_9") (pintype "passive"))
      (node (ref "P14") (pin "2") (pinfunction "2_2") (pintype "passive"))
      (node (ref "P15") (pin "3") (pinfunction "3_3") (pintype "passive"))
      (node (ref "P2") (pin "1") (pinfunction "1_1") (pintype "passive"))
      (node (ref "P3") (pin "3") (pinfunction "3_3") (pintype "passive"))
      (node (ref "P3") (pin "5") (pinfunction "5_5") (pintype "passive"))
      (node (ref "P4") (pin "1") (pinfunction "1_1") (pintype "passive"))
      (node (ref "P5") (pin "1") (pinfunction "1_1") (pintype "passive"))
      (node (ref "P6") (pin "1") (pinfunction "1_1") (pintype "passive"))
      (node (ref "P7") (pin "1") (pinfunction "1_1") (pintype "passive"))
      (node (ref "SW1") (pin "2") (pintype "passive"))
      (node (ref "U1") (pin "2") (pinfunction "VSS_2") (pintype "passive"))
      (node (ref "U1") (pin "33") (pinfunction "GND_-_PAD_33") (pintype "passive"))
      (node (ref "U1") (pin "8") (pinfunction "VSSA_8") (pintype "passive"))
      (node (ref "U2") (pin "15") (pinfunction "GND-PAD_15") (pintype "passive"))
      (node (ref "U2") (pin "7") (pinfunction "GND_7") (pintype "passive"))
      (node (ref "U3") (pin "8") (pinfunction "GND_8") (pintype "passive"))
      (node (ref "U4") (pin "15") (pinfunction "GND_15") (pintype "input"))
      (node (ref "U5") (pin "1") (pinfunction "PGND_1") (pintype "passive"))
      (node (ref "U5") (pin "4") (pinfunction "AGND_4") (pintype "passive"))
      (node (ref "U5") (pin "5") (pinfunction "FB_5") (pintype "passive"))
      (node (ref "U5") (pin "9") (pinfunction "GND/THERMAL_9") (pintype "passive"))
      (node (ref "U6") (pin "1") (pinfunction "PGND_1") (pintype "passive"))
      (node (ref "U6") (pin "4") (pinfunction "AGND_4") (pintype "passive"))
      (node (ref "U6") (pin "5") (pinfunction "FB_5") (pintype "passive"))
      (node (ref "U6") (pin "9") (pinfunction "GND/THERMAL_9") (pintype "passive"))
    )
    (net (code "53") (name "Net-(D2-PadA)") (class "Default")
      (node (ref "D2") (pin "A") (pinfunction "A_A") (pintype "passive"))
      (node (ref "R14") (pin "2") (pinfunction "2_2") (pintype "passive"))
    )
    (net (code "54") (name "Net-(D3-PadA)") (class "Default")
      (node (ref "D3") (pin "A") (pinfunction "A_A") (pintype "passive"))
      (node (ref "R13") (pin "2") (pinfunction "2_2") (pintype "passive"))
    )
    (net (code "55") (name "Net-(U1-VDDA)") (class "Default")
      (node (ref "C11") (pin "2") (pinfunction "2_2") (pintype "passive"))
      (node (ref "FB1") (pin "2") (pinfunction "2_2") (pintype "passive"))
      (node (ref "U1") (pin "7") (pinfunction "VDDA_7") (pintype "passive"))
    )
    (net (code "56") (name "Net-(U4-EN)") (class "Default")
      (node (ref "R5") (pin "2") (pinfunction "2_2") (pintype "passive"))
      (node (ref "U4") (pin "3") (pinfunction "EN_3") (pintype "input"))
    )
    (net (code "57") (name "Net-(U4-GPIO4)") (class "Default")
      (node (ref "P12") (pin "4") (pinfunction "4_4") (pintype "passive"))
      (node (ref "U4") (pin "19") (pinfunction "GPIO4_19") (pintype "passive"))
    )
    (net (code "58") (name "Net-(U4-GPIO5)") (class "Default")
      (node (ref "P12") (pin "3") (pinfunction "3_3") (pintype "passive"))
      (node (ref "U4") (pin "20") (pinfunction "GPIO5_20") (pintype "passive"))
    )
    (net (code "59") (name "Net-(U4-RXD0)") (class "Default")
      (node (ref "P12") (pin "2") (pinfunction "2_2") (pintype "passive"))
      (node (ref "U4") (pin "21") (pinfunction "RXD0_21") (pintype "passive"))
    )
    (net (code "60") (name "Net-(U4-TXD0)") (class "Default")
      (node (ref "P12") (pin "1") (pinfunction "1_1") (pintype "passive"))
      (node (ref "U4") (pin "22") (pinfunction "TXD0_22") (pintype "passive"))
    )
    (net (code "61") (name "Net-(U5-PG)") (class "Default")
      (node (ref "R1") (pin "1") (pinfunction "1_1") (pintype "passive"))
      (node (ref "U5") (pin "8") (pinfunction "PG_8") (pintype "passive"))
    )
    (net (code "62") (name "Net-(U5-SW)") (class "Default")
      (node (ref "L1") (pin "1") (pinfunction "1_1") (pintype "passive"))
      (node (ref "U5") (pin "7") (pinfunction "SW_7") (pintype "passive"))
    )
    (net (code "63") (name "Net-(U6-PG)") (class "Default")
      (node (ref "R2") (pin "1") (pinfunction "1_1") (pintype "passive"))
      (node (ref "U6") (pin "8") (pinfunction "PG_8") (pintype "passive"))
    )
    (net (code "64") (name "Net-(U6-SW)") (class "Default")
      (node (ref "L2") (pin "1") (pinfunction "1_1") (pintype "passive"))
      (node (ref "U6") (pin "7") (pinfunction "SW_7") (pintype "passive"))
    )
    (net (code "65") (name "unconnected-(J1-Pad7)") (class "Default")
      (node (ref "J1") (pin "7") (pinfunction "7_7") (pintype "passive+no_connect"))
    )
    (net (code "66") (name "unconnected-(P3-Pad4)") (class "Default")
      (node (ref "P3") (pin "4") (pinfunction "4_4") (pintype "passive"))
    )
    (net (code "67") (name "unconnected-(U1-PTC2_ADC0_SE11_{slash}_SPI0_CS2_{slash}_UART1_CTS_{slash}_FTM0_CH1_{slash}_FTM2_CH1-Pad23)") (class "Default")
      (node (ref "U1") (pin "23") (pinfunction "PTC2_ADC0_SE11_/_SPI0_CS2_/_UART1_CTS_/_FTM0_CH1_/_FTM2_CH1_23") (pintype "passive"))
    )
    (net (code "68") (name "unconnected-(U1-PTC3_CMP1_IN1_{slash}__LLWU_P7_{slash}_SPI0_CS1_{slash}_UART1_RX_{slash}_FTM0_CH2_{slash}_CLKOUT-Pad24)") (class "Default")
      (node (ref "U1") (pin "24") (pinfunction "PTC3_CMP1_IN1_/__LLWU_P7_/_SPI0_CS1_/_UART1_RX_/_FTM0_CH2_/_CLKOUT_24") (pintype "passive"))
    )
    (net (code "69") (name "unconnected-(U1-PTE30_ADC1_SE4_{slash}_DAC0_OUT_{slash}_FTM0_CH3-Pad9)") (class "Default")
      (node (ref "U1") (pin "9") (pinfunction "PTE30_ADC1_SE4_/_DAC0_OUT_/_FTM0_CH3_9") (pintype "passive"))
    )
    (net (code "70") (name "unconnected-(U2-NC-Pad6)") (class "Default")
      (node (ref "U2") (pin "6") (pinfunction "NC_6") (pintype "passive"))
    )
    (net (code "71") (name "unconnected-(U2-NC-Pad9)") (class "Default")
      (node (ref "U2") (pin "9") (pinfunction "NC_9") (pintype "passive"))
    )
    (net (code "72") (name "unconnected-(U3-S0-Pad10)") (class "Default")
      (node (ref "U3") (pin "10") (pinfunction "S0_10") (pintype "passive"))
    )
    (net (code "73") (name "unconnected-(U3-S1-Pad9)") (class "Default")
      (node (ref "U3") (pin "9") (pinfunction "S1_9") (pintype "passive"))
    )
    (net (code "74") (name "unconnected-(U3-VEE-Pad7)") (class "Default")
      (node (ref "U3") (pin "7") (pinfunction "VEE_7") (pintype "passive"))
    )
    (net (code "75") (name "unconnected-(U3-~{E}-Pad6)") (class "Default")
      (node (ref "U3") (pin "6") (pinfunction "~{E}_6") (pintype "passive"))
    )
    (net (code "76") (name "unconnected-(U4-GPIO9-Pad11)") (class "Default")
      (node (ref "U4") (pin "11") (pinfunction "GPIO9_11") (pintype "bidirectional"))
    )
    (net (code "77") (name "unconnected-(U4-GPIO10-Pad12)") (class "Default")
      (node (ref "U4") (pin "12") (pinfunction "GPIO10_12") (pintype "bidirectional"))
    )
  )
)
